# OSHW-RGB-Badge_v11.net
KiCad netlist of a schematic drawn in EAGLE
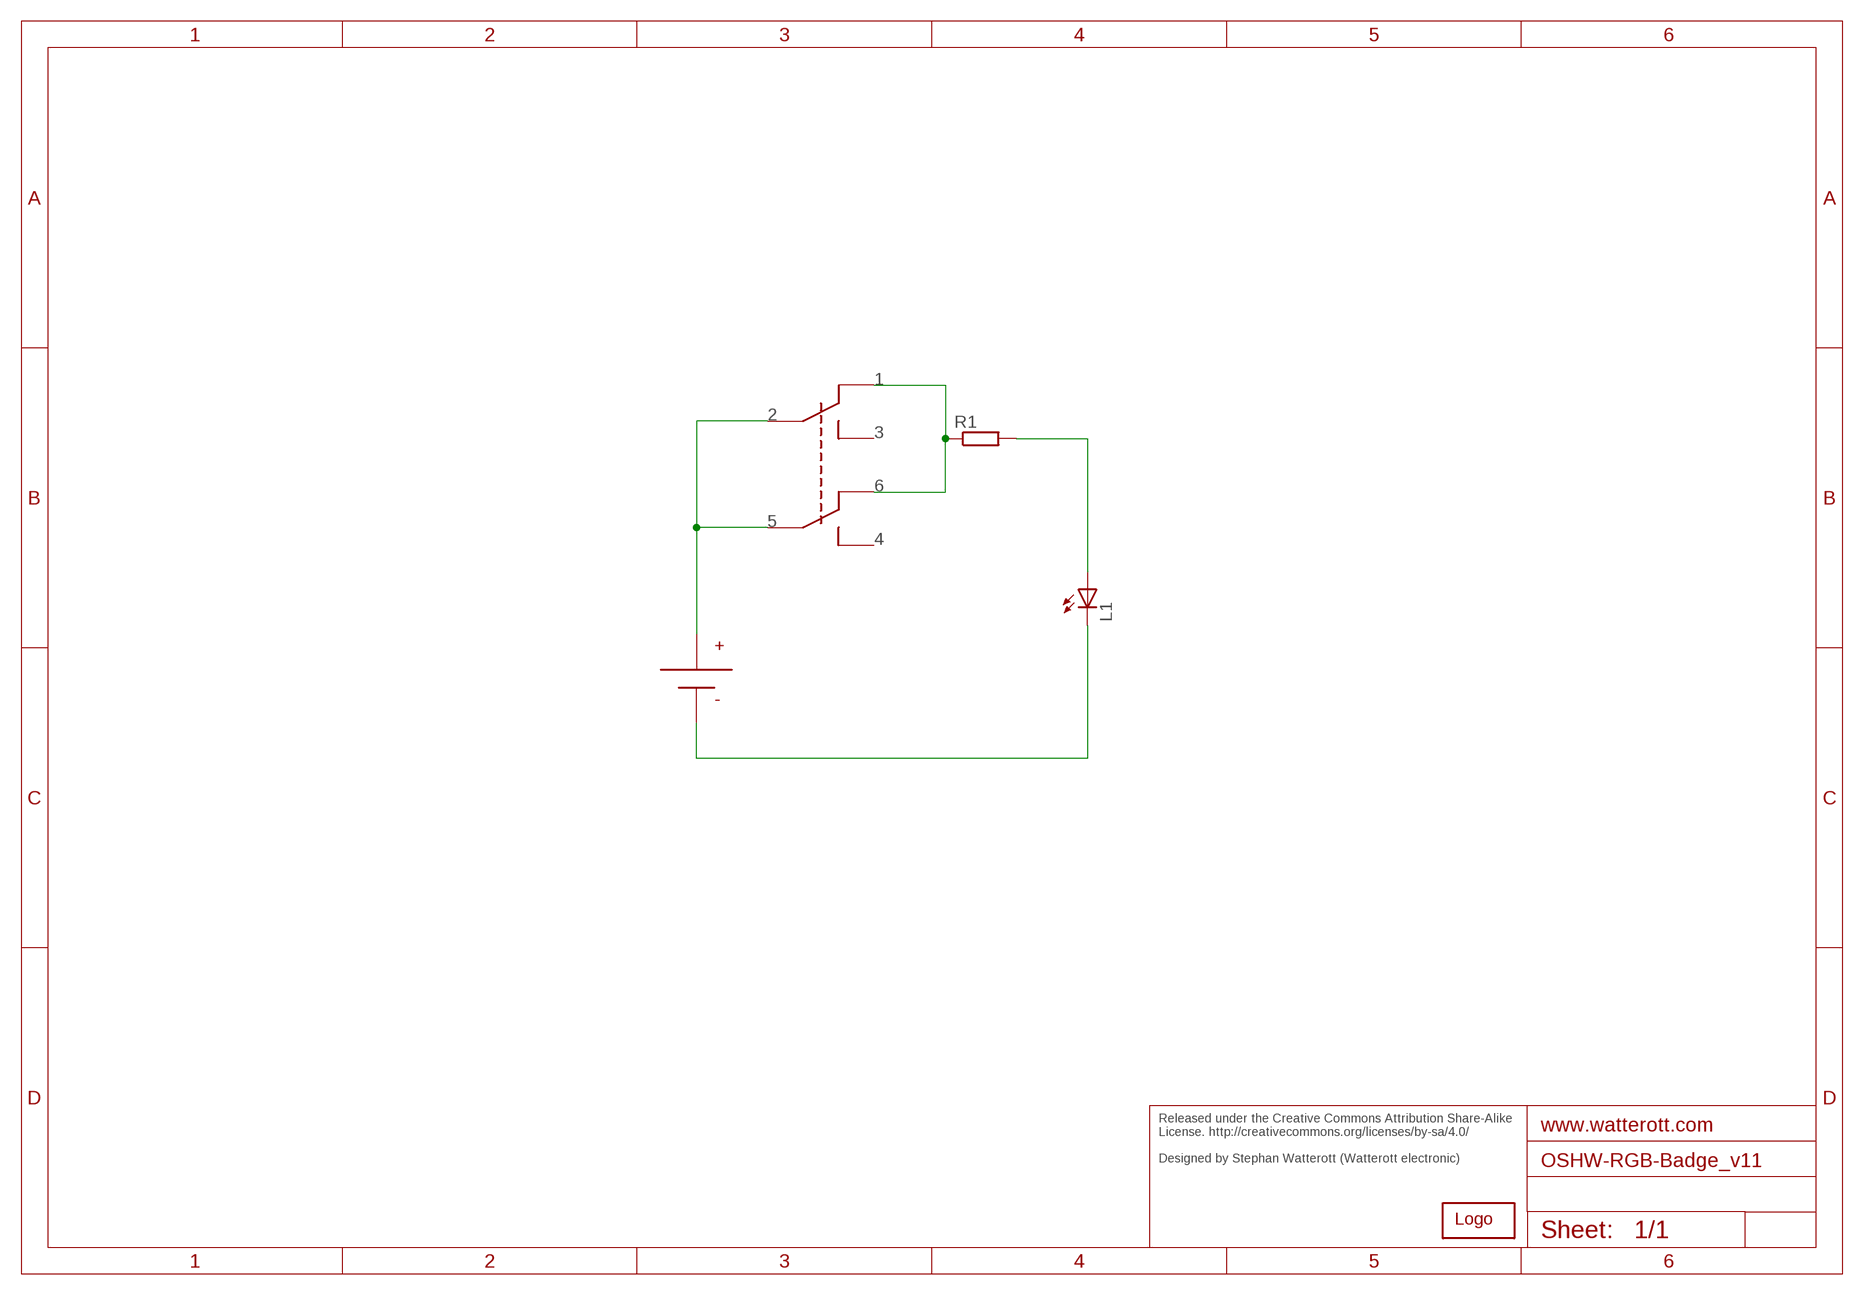
[diagram p0: schematic, sheet 1]

(export (version "E")
  (design (tool "Eeschema 10.0.6"))
  (components
    (comp (ref "BAT")
      (value "CN2032_BATTERY_HOLDER")
      (footprint "eagle-import:CN2032_BATTERY_HOLDER")
      (libsource (lib "eagle-import") (part "CN2032_BATTERY_HOLDER"))
    )
    (comp (ref "L1")
      (value "LED10MM")
      (footprint "eagle-import:LED10MM")
      (libsource (lib "eagle-import") (part "LED10MM"))
    )
    (comp (ref "LOGO3")
      (value "LOGO-SPARK_PLACE")
      (footprint "eagle-import:SPARK_TPLACE")
      (libsource (lib "eagle-import") (part "LOGO-SPARK_PLACE"))
    )
    (comp (ref "R1")
      (value "R-EU_0207/7")
      (footprint "eagle-import:0207_7")
      (libsource (lib "eagle-import") (part "R-EU_0207/7"))
    )
    (comp (ref "SW")
      (value "SWITCH_6-POL_RM2.54")
      (footprint "eagle-import:SWITCH_6POL_RM2.54")
      (libsource (lib "eagle-import") (part "SWITCH_6-POL_RM2.54"))
    )
  )
  (nets
    (net (code "1") (name "Net-(BAT-+)") (class "Default")
      (node (ref "BAT") (pin "P$1") (pinfunction "+_P$1") (pintype "bidirectional"))
      (node (ref "SW") (pin "P$2") (pinfunction "P$2_P$2") (pintype "bidirectional"))
      (node (ref "SW") (pin "P$5") (pinfunction "P$5_P$5") (pintype "bidirectional"))
    )
    (net (code "2") (name "Net-(BAT--)") (class "Default")
      (node (ref "BAT") (pin "P$2") (pinfunction "-_P$2") (pintype "bidirectional"))
      (node (ref "L1") (pin "K") (pinfunction "C_K") (pintype "passive"))
    )
    (net (code "3") (name "Net-(L1-PadA)") (class "Default")
      (node (ref "L1") (pin "A") (pinfunction "A_A") (pintype "passive"))
      (node (ref "R1") (pin "2") (pinfunction "2_2") (pintype "passive"))
    )
    (net (code "4") (name "Net-(R1-Pad1)") (class "Default")
      (node (ref "R1") (pin "1") (pinfunction "1_1") (pintype "passive"))
      (node (ref "SW") (pin "P$1") (pinfunction "P$1_P$1") (pintype "bidirectional"))
      (node (ref "SW") (pin "P$6") (pinfunction "P$6_P$6") (pintype "bidirectional"))
    )
    (net (code "5") (name "unconnected-(SW-PadP$3)") (class "Default")
      (node (ref "SW") (pin "P$3") (pinfunction "P$3_P$3") (pintype "bidirectional"))
    )
    (net (code "6") (name "unconnected-(SW-PadP$4)") (class "Default")
      (node (ref "SW") (pin "P$4") (pinfunction "P$4_P$4") (pintype "bidirectional"))
    )
  )
)
